# Power_Distribution_Block_Diagram.net
KiCad netlist of a schematic drawn in Altium Designer
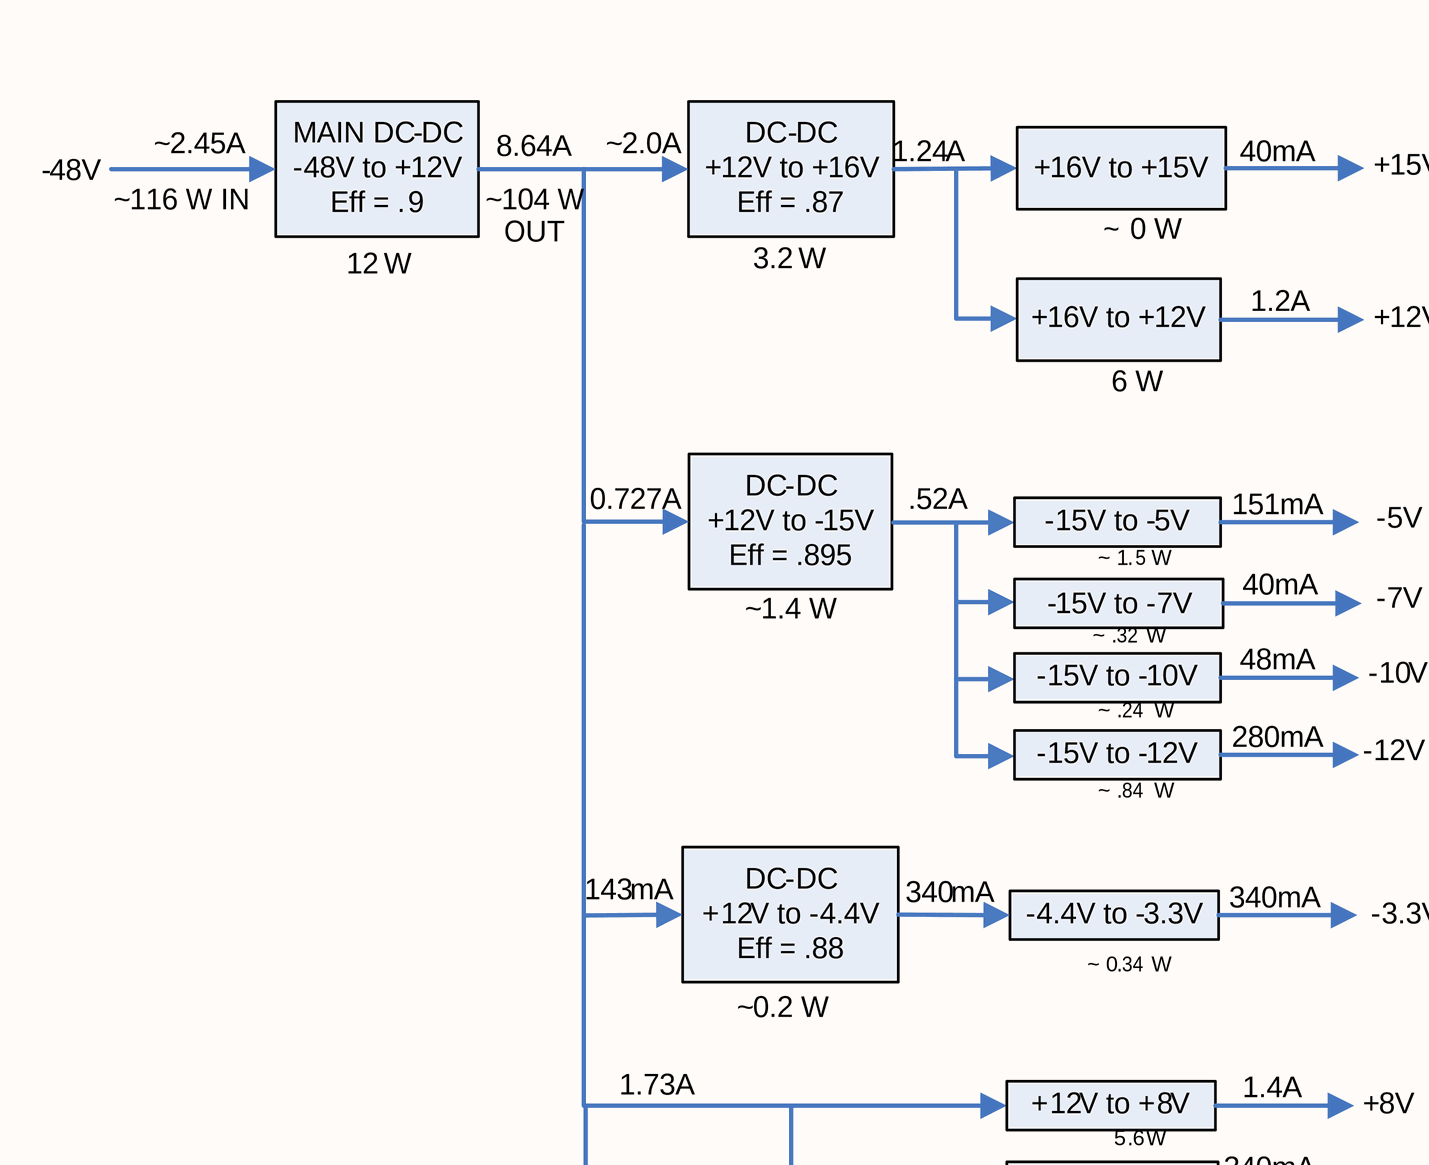
[diagram p0: Power Distribution Block Diagram.SchDoc, top left]
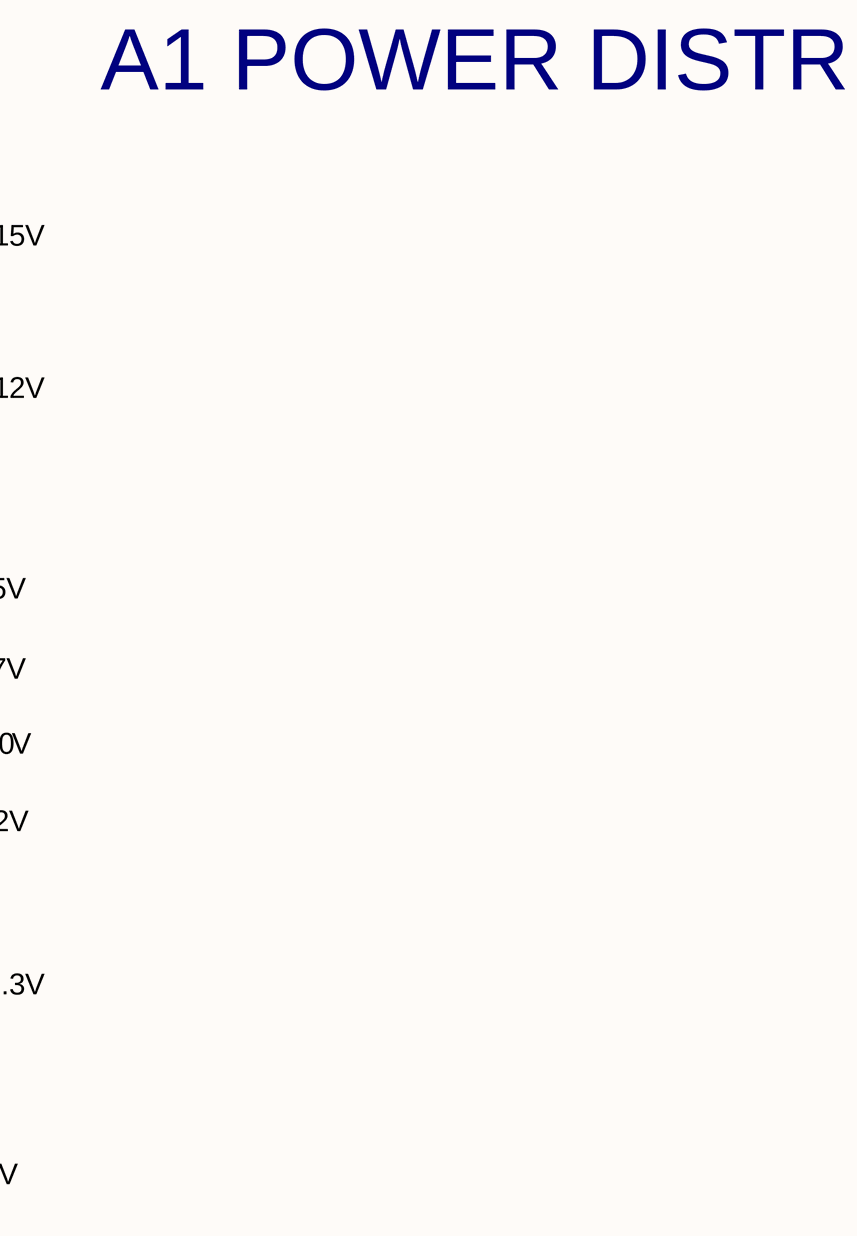
[diagram p1: Power Distribution Block Diagram.SchDoc, top middle]
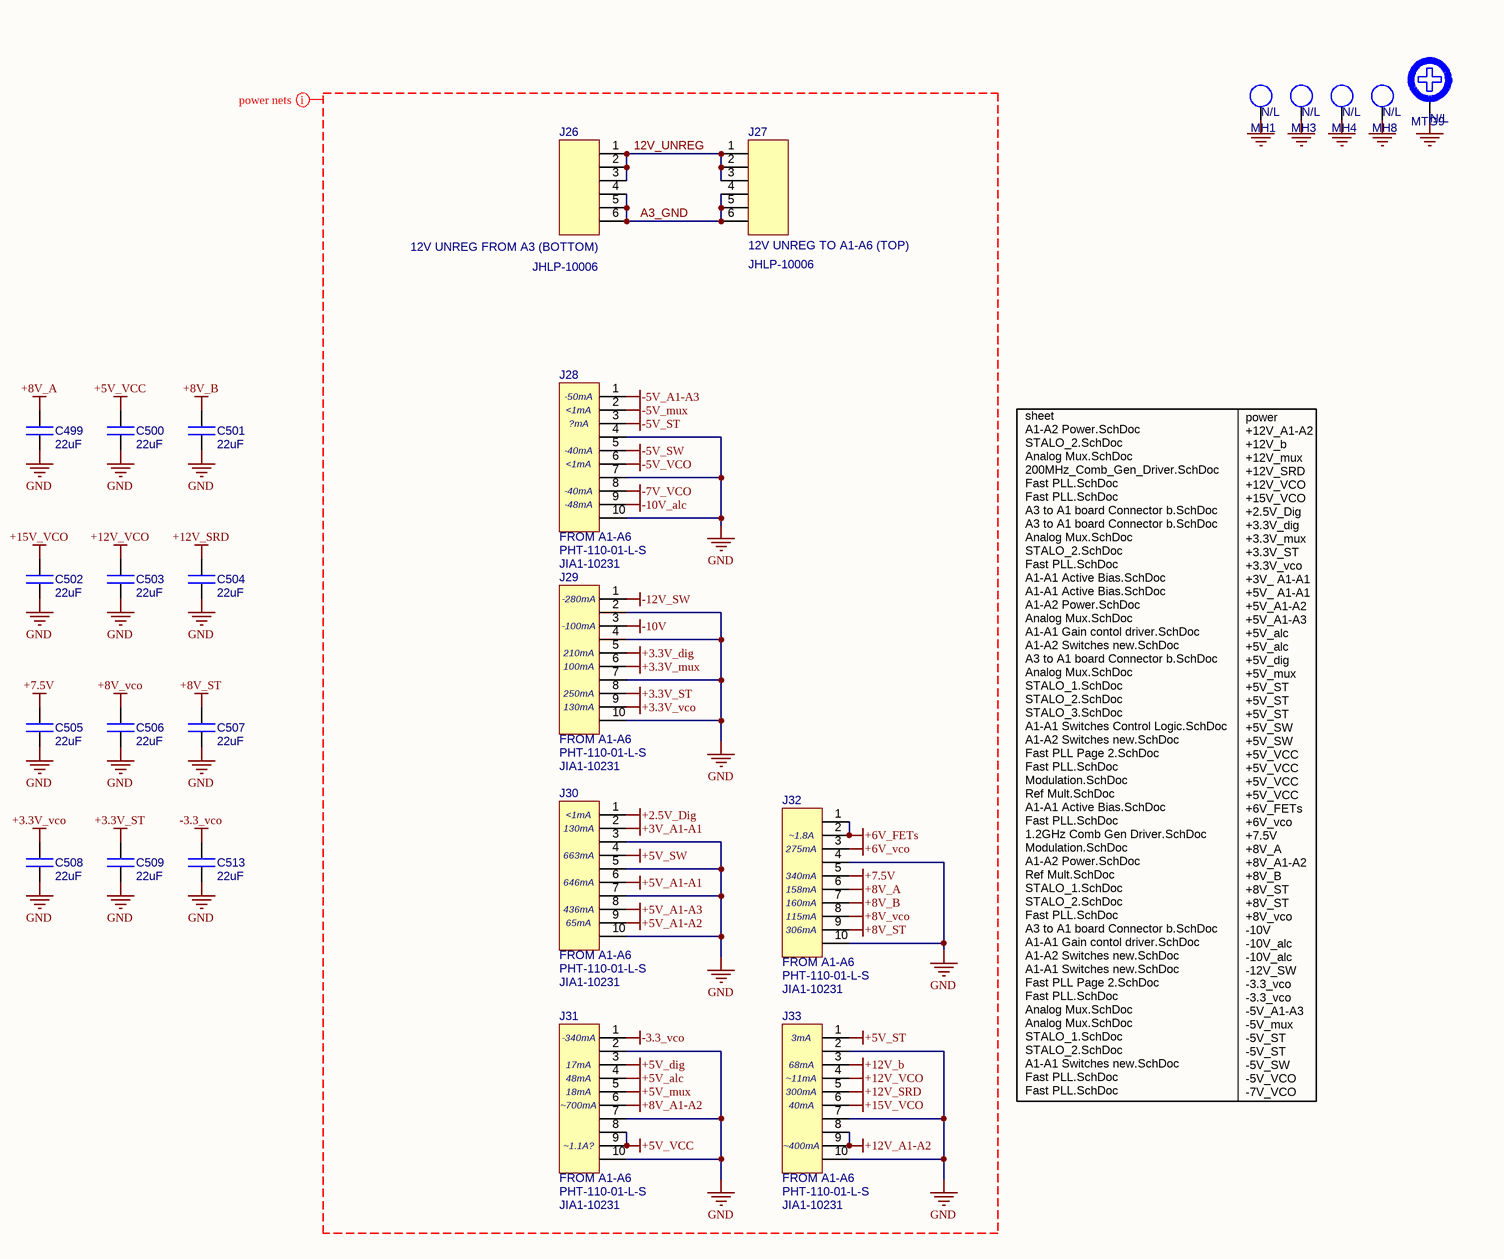
[diagram p2: Power Distribution Block Diagram.SchDoc, top right]
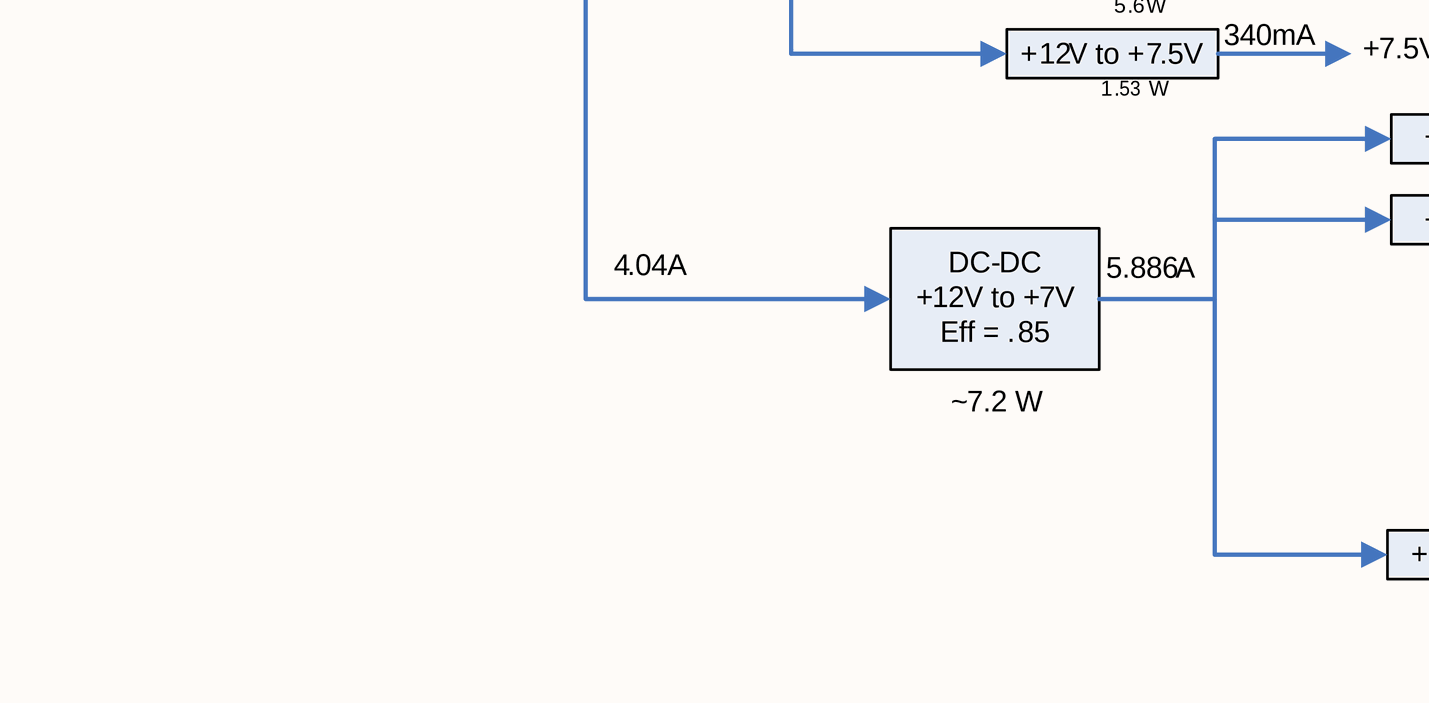
[diagram p3: Power Distribution Block Diagram.SchDoc, bottom left]
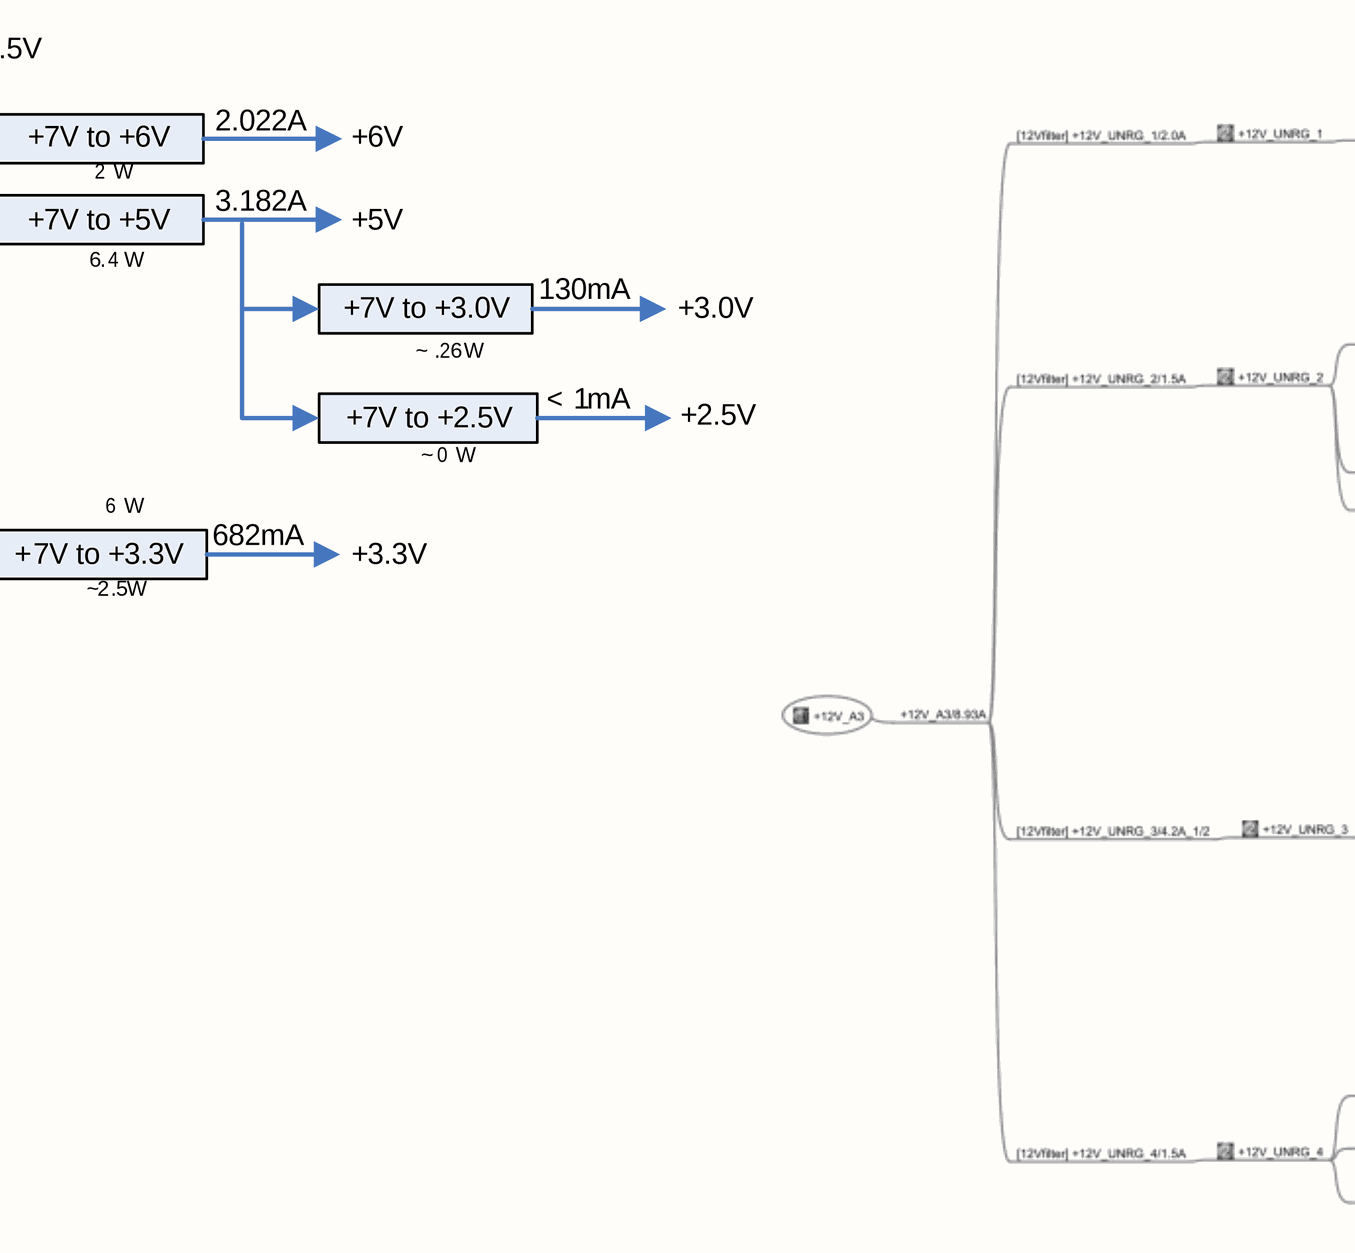
[diagram p4: Power Distribution Block Diagram.SchDoc, bottom middle]
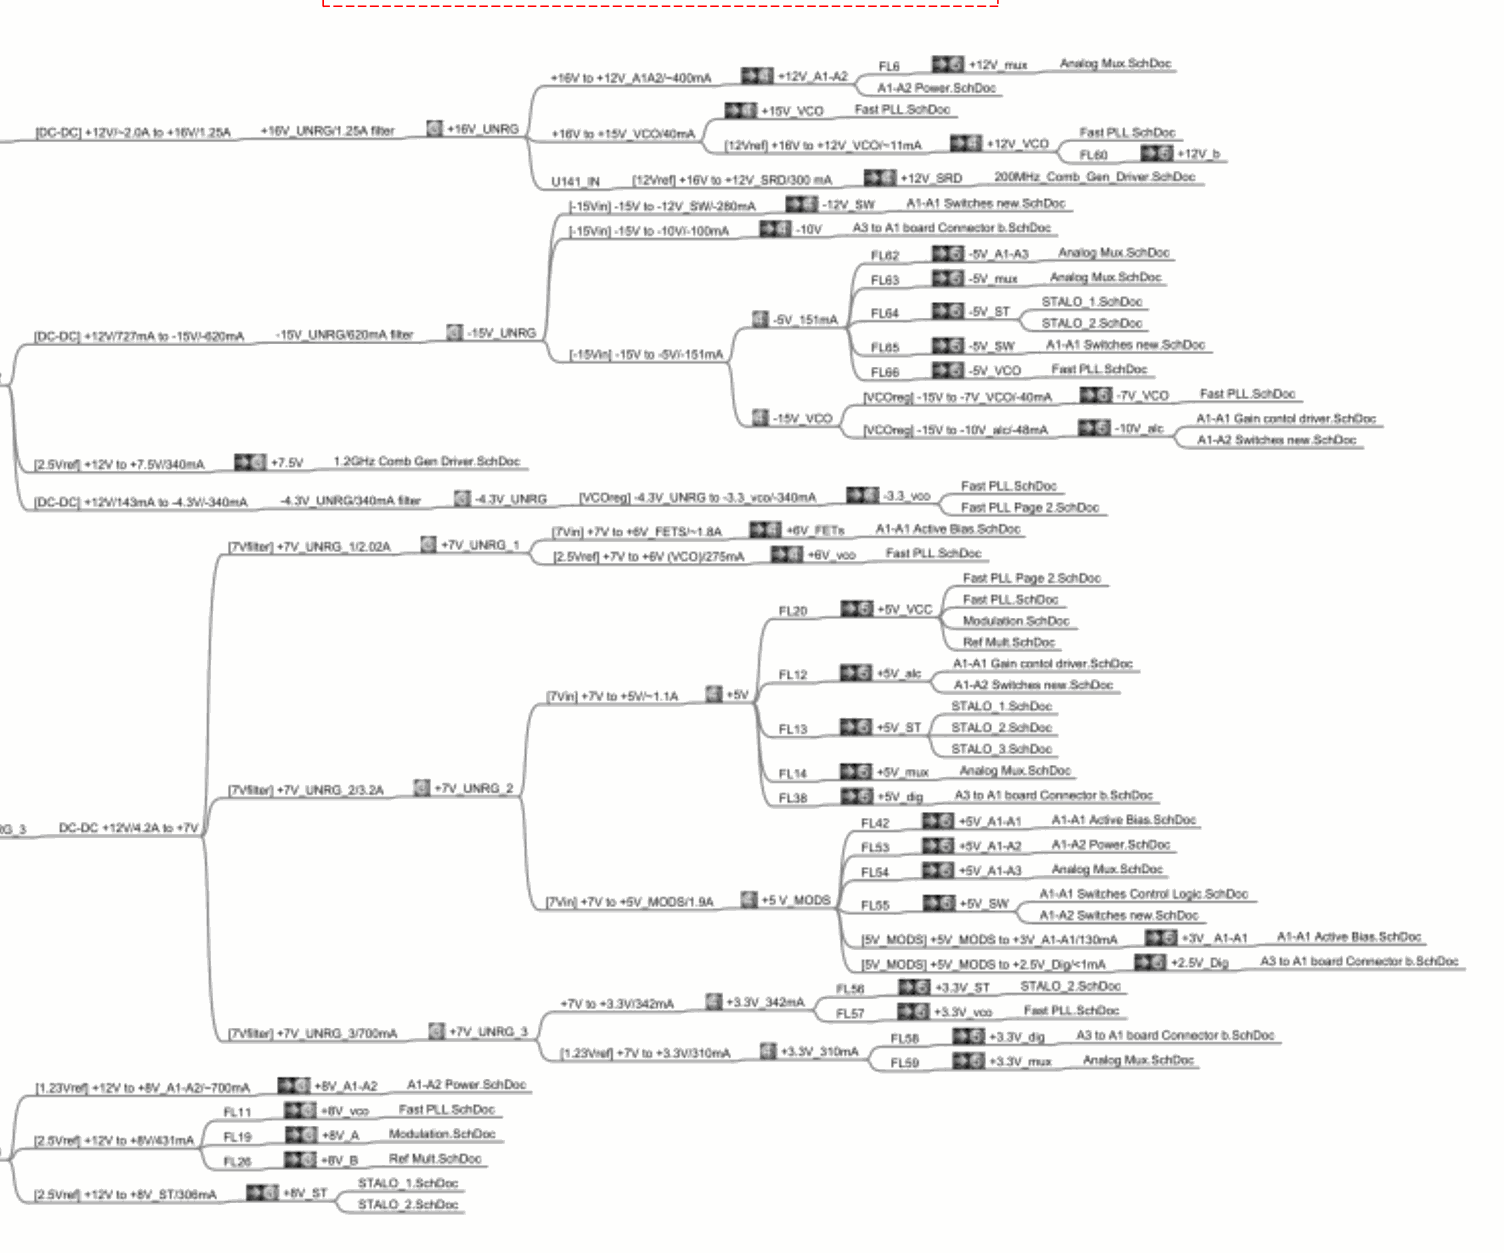
[diagram p5: Power Distribution Block Diagram.SchDoc, bottom right]

(export (version "E")
  (design (tool "Eeschema 10.0.6"))
  (components
    (comp (ref "C499")
      (value "22uF")
      (footprint "CAP-1210-N")
      (description "22uF;X5R;CERAMIC CHIP;25V;1210")
      (fields (field (name "APPROVED") "CL"))
      (libsource (lib "Giga-tronics") (part "CK60-26220"))
    )
    (comp (ref "C500")
      (value "22uF")
      (footprint "CAP-1210-N")
      (description "22uF;X5R;CERAMIC CHIP;25V;1210")
      (fields (field (name "APPROVED") "CL"))
      (libsource (lib "Giga-tronics") (part "CK60-26220"))
    )
    (comp (ref "C501")
      (value "22uF")
      (footprint "CAP-1210-N")
      (description "22uF;X5R;CERAMIC CHIP;25V;1210")
      (fields (field (name "APPROVED") "CL"))
      (libsource (lib "Giga-tronics") (part "CK60-26220"))
    )
    (comp (ref "C502")
      (value "22uF")
      (footprint "CAP-1210-N")
      (description "22uF;X5R;CERAMIC CHIP;25V;1210")
      (fields (field (name "APPROVED") "CL"))
      (libsource (lib "Giga-tronics") (part "CK60-26220"))
    )
    (comp (ref "C503")
      (value "22uF")
      (footprint "CAP-1210-N")
      (description "22uF;X5R;CERAMIC CHIP;25V;1210")
      (fields (field (name "APPROVED") "CL"))
      (libsource (lib "Giga-tronics") (part "CK60-26220"))
    )
    (comp (ref "C504")
      (value "22uF")
      (footprint "CAP-1210-N")
      (description "22uF;X5R;CERAMIC CHIP;25V;1210")
      (fields (field (name "APPROVED") "CL"))
      (libsource (lib "Giga-tronics") (part "CK60-26220"))
    )
    (comp (ref "C505")
      (value "22uF")
      (footprint "CAP-1210-N")
      (description "22uF;X5R;CERAMIC CHIP;25V;1210")
      (fields (field (name "APPROVED") "CL"))
      (libsource (lib "Giga-tronics") (part "CK60-26220"))
    )
    (comp (ref "C506")
      (value "22uF")
      (footprint "CAP-1210-N")
      (description "22uF;X5R;CERAMIC CHIP;25V;1210")
      (fields (field (name "APPROVED") "CL"))
      (libsource (lib "Giga-tronics") (part "CK60-26220"))
    )
    (comp (ref "C507")
      (value "22uF")
      (footprint "CAP-1210-N")
      (description "22uF;X5R;CERAMIC CHIP;25V;1210")
      (fields (field (name "APPROVED") "CL"))
      (libsource (lib "Giga-tronics") (part "CK60-26220"))
    )
    (comp (ref "C508")
      (value "22uF")
      (footprint "CAP-1210-N")
      (description "22uF;X5R;CERAMIC CHIP;25V;1210")
      (fields (field (name "APPROVED") "CL"))
      (libsource (lib "Giga-tronics") (part "CK60-26220"))
    )
    (comp (ref "C509")
      (value "22uF")
      (footprint "CAP-1210-N")
      (description "22uF;X5R;CERAMIC CHIP;25V;1210")
      (fields (field (name "APPROVED") "CL"))
      (libsource (lib "Giga-tronics") (part "CK60-26220"))
    )
    (comp (ref "C513")
      (value "22uF")
      (footprint "CAP-1210-N")
      (description "22uF;X5R;CERAMIC CHIP;25V;1210")
      (fields (field (name "APPROVED") "CL"))
      (libsource (lib "Giga-tronics") (part "CK60-26220"))
    )
    (comp (ref "J26")
      (value "12V UNREG FROM A3 (BOTTOM)")
      (footprint "JHLP-10006")
      (description "LOCKING HEADER;.1CNTR;6PIN STR")
      (fields (field (name "G_PN") "JHLP-10006") (field (name "APPROVED") "FV"))
      (libsource (lib "") (part "JHLP-10006_1"))
    )
    (comp (ref "J27")
      (value "12V UNREG TO A1-A6 (TOP)")
      (footprint "JHLP-10006")
      (description "LOCKING HEADER;.1CNTR;6PIN STR")
      (fields (field (name "G_PN") "JHLP-10006") (field (name "APPROVED") "FV"))
      (libsource (lib "Giga-tronics") (part "JHLP-10006"))
    )
    (comp (ref "J28")
      (value "FROM A1-A6")
      (footprint "JIA1-10231")
      (description "STRIPLINE PLUG;.1 CTR;10 PIN;SINGLE ROW;.230;PRESS FIT;GOLD")
      (fields (field (name "M_PN") "PHT-110-01-L-S") (field (name "G_PN") "JIA1-10231"))
      (libsource (lib "Giga-tronics") (part "JIA1-10231"))
    )
    (comp (ref "J29")
      (value "FROM A1-A6")
      (footprint "JIA1-10231")
      (description "STRIPLINE PLUG;.1 CTR;10 PIN;SINGLE ROW;.230;PRESS FIT;GOLD")
      (fields (field (name "M_PN") "PHT-110-01-L-S") (field (name "G_PN") "JIA1-10231"))
      (libsource (lib "Giga-tronics") (part "JIA1-10231"))
    )
    (comp (ref "J30")
      (value "FROM A1-A6")
      (footprint "JIA1-10231")
      (description "STRIPLINE PLUG;.1 CTR;10 PIN;SINGLE ROW;.230;PRESS FIT;GOLD")
      (fields (field (name "M_PN") "PHT-110-01-L-S") (field (name "G_PN") "JIA1-10231"))
      (libsource (lib "Giga-tronics") (part "JIA1-10231"))
    )
    (comp (ref "J31")
      (value "FROM A1-A6")
      (footprint "JIA1-10231")
      (description "STRIPLINE PLUG;.1 CTR;10 PIN;SINGLE ROW;.230;PRESS FIT;GOLD")
      (fields (field (name "M_PN") "PHT-110-01-L-S") (field (name "G_PN") "JIA1-10231"))
      (libsource (lib "Giga-tronics") (part "JIA1-10231"))
    )
    (comp (ref "J32")
      (value "FROM A1-A6")
      (footprint "JIA1-10231")
      (description "STRIPLINE PLUG;.1 CTR;10 PIN;SINGLE ROW;.230;PRESS FIT;GOLD")
      (fields (field (name "M_PN") "PHT-110-01-L-S") (field (name "G_PN") "JIA1-10231"))
      (libsource (lib "Giga-tronics") (part "JIA1-10231"))
    )
    (comp (ref "J33")
      (value "FROM A1-A6")
      (footprint "JIA1-10231")
      (description "STRIPLINE PLUG;.1 CTR;10 PIN;SINGLE ROW;.230;PRESS FIT;GOLD")
      (fields (field (name "M_PN") "PHT-110-01-L-S") (field (name "G_PN") "JIA1-10231"))
      (libsource (lib "Giga-tronics") (part "JIA1-10231"))
    )
    (comp (ref "MH1")
      (value "N/L")
      (footprint "MHP-250X116")
      (description "MHP-250X116")
      (fields (field (name "NOLOAD") "N/L"))
      (libsource (lib "Giga-tronics") (part "MHP-250X116"))
    )
    (comp (ref "MH3")
      (value "N/L")
      (footprint "MHP-250X116")
      (description "MHP-250X116")
      (fields (field (name "NOLOAD") "N/L"))
      (libsource (lib "Giga-tronics") (part "MHP-250X116"))
    )
    (comp (ref "MH4")
      (value "N/L")
      (footprint "MHP-250X116")
      (description "MHP-250X116")
      (fields (field (name "NOLOAD") "N/L"))
      (libsource (lib "Giga-tronics") (part "MHP-250X116"))
    )
    (comp (ref "MH8")
      (value "N/L")
      (footprint "MHP-250X116")
      (description "MHP-250X116")
      (fields (field (name "NOLOAD") "N/L"))
      (libsource (lib "Giga-tronics") (part "MHP-250X116"))
    )
    (comp (ref "MTG9")
      (value "~")
      (footprint "MHP-250X116")
      (description "MHP250X116")
      (fields (field (name "NOLOAD") "N/L"))
      (libsource (lib "Giga-tronics") (part "MHP250X116"))
    )
  )
  (nets
    (net (code "1") (name "+2.5V_Dig") (class "Default") (node (ref "J30") (pin "1") (pintype "passive")))
    (net (code "2") (name "+3.3V_ST") (class "Default")
      (node (ref "C509") (pin "2") (pintype "passive"))
      (node (ref "J29") (pin "8") (pintype "passive"))
    )
    (net (code "3") (name "+3.3V_dig") (class "Default") (node (ref "J29") (pin "5") (pintype "passive")))
    (net (code "4") (name "+3.3V_mux") (class "Default") (node (ref "J29") (pin "6") (pintype "passive")))
    (net (code "5") (name "+3.3V_vco") (class "Default")
      (node (ref "C508") (pin "2") (pintype "passive"))
      (node (ref "J29") (pin "9") (pintype "passive"))
    )
    (net (code "6") (name "+3V_A1-A1") (class "Default") (node (ref "J30") (pin "2") (pintype "passive")))
    (net (code "7") (name "+5V_A1-A1") (class "Default") (node (ref "J30") (pin "6") (pintype "passive")))
    (net (code "8") (name "+5V_A1-A2") (class "Default") (node (ref "J30") (pin "9") (pintype "passive")))
    (net (code "9") (name "+5V_A1-A3") (class "Default") (node (ref "J30") (pin "8") (pintype "passive")))
    (net (code "10") (name "+5V_ST") (class "Default") (node (ref "J33") (pin "1") (pintype "passive")))
    (net (code "11") (name "+5V_SW") (class "Default") (node (ref "J30") (pin "4") (pintype "passive")))
    (net (code "12") (name "+5V_VCC") (class "Default")
      (node (ref "C500") (pin "2") (pintype "passive"))
      (node (ref "J31") (pin "8") (pintype "passive"))
      (node (ref "J31") (pin "9") (pintype "passive"))
    )
    (net (code "13") (name "+5V_alc") (class "Default") (node (ref "J31") (pin "4") (pintype "passive")))
    (net (code "14") (name "+5V_dig") (class "Default") (node (ref "J31") (pin "3") (pintype "passive")))
    (net (code "15") (name "+5V_mux") (class "Default") (node (ref "J31") (pin "5") (pintype "passive")))
    (net (code "16") (name "+6V_FETs") (class "Default")
      (node (ref "J32") (pin "1") (pintype "passive"))
      (node (ref "J32") (pin "2") (pintype "passive"))
    )
    (net (code "17") (name "+6V_vco") (class "Default") (node (ref "J32") (pin "3") (pintype "passive")))
    (net (code "18") (name "+7.5V") (class "Default")
      (node (ref "C505") (pin "2") (pintype "passive"))
      (node (ref "J32") (pin "5") (pintype "passive"))
    )
    (net (code "19") (name "+8V_A") (class "Default")
      (node (ref "C499") (pin "2") (pintype "passive"))
      (node (ref "J32") (pin "6") (pintype "passive"))
    )
    (net (code "20") (name "+8V_A1-A2") (class "Default") (node (ref "J31") (pin "6") (pintype "passive")))
    (net (code "21") (name "+8V_B") (class "Default")
      (node (ref "C501") (pin "2") (pintype "passive"))
      (node (ref "J32") (pin "7") (pintype "passive"))
    )
    (net (code "22") (name "+8V_ST") (class "Default")
      (node (ref "C507") (pin "2") (pintype "passive"))
      (node (ref "J32") (pin "9") (pintype "passive"))
    )
    (net (code "23") (name "+8V_vco") (class "Default")
      (node (ref "C506") (pin "2") (pintype "passive"))
      (node (ref "J32") (pin "8") (pintype "passive"))
    )
    (net (code "24") (name "+12V_A1-A2") (class "Default")
      (node (ref "J33") (pin "8") (pintype "passive"))
      (node (ref "J33") (pin "9") (pintype "passive"))
    )
    (net (code "25") (name "+12V_SRD") (class "Default")
      (node (ref "C504") (pin "2") (pintype "passive"))
      (node (ref "J33") (pin "5") (pintype "passive"))
    )
    (net (code "26") (name "+12V_VCO") (class "Default")
      (node (ref "C503") (pin "2") (pintype "passive"))
      (node (ref "J33") (pin "4") (pintype "passive"))
    )
    (net (code "27") (name "+12V_b") (class "Default") (node (ref "J33") (pin "3") (pintype "passive")))
    (net (code "28") (name "+15V_VCO") (class "Default")
      (node (ref "C502") (pin "2") (pintype "passive"))
      (node (ref "J33") (pin "6") (pintype "passive"))
    )
    (net (code "29") (name "-3.3_vco") (class "Default")
      (node (ref "C513") (pin "2") (pintype "passive"))
      (node (ref "J31") (pin "1") (pintype "passive"))
    )
    (net (code "30") (name "-5V_A1-A3") (class "Default") (node (ref "J28") (pin "1") (pintype "passive")))
    (net (code "31") (name "-5V_ST") (class "Default") (node (ref "J28") (pin "3") (pintype "passive")))
    (net (code "32") (name "-5V_SW") (class "Default") (node (ref "J28") (pin "5") (pintype "passive")))
    (net (code "33") (name "-5V_VCO") (class "Default") (node (ref "J28") (pin "6") (pintype "passive")))
    (net (code "34") (name "-5V_mux") (class "Default") (node (ref "J28") (pin "2") (pintype "passive")))
    (net (code "35") (name "-7V_VCO") (class "Default") (node (ref "J28") (pin "8") (pintype "passive")))
    (net (code "36") (name "-10V") (class "Default") (node (ref "J29") (pin "3") (pintype "passive")))
    (net (code "37") (name "-10V_alc") (class "Default") (node (ref "J28") (pin "9") (pintype "passive")))
    (net (code "38") (name "-12V_SW") (class "Default") (node (ref "J29") (pin "1") (pintype "passive")))
    (net (code "39") (name "/12V_UNREG") (class "Default")
      (node (ref "J26") (pin "1") (pintype "passive"))
      (node (ref "J26") (pin "2") (pintype "passive"))
      (node (ref "J26") (pin "3") (pintype "passive"))
      (node (ref "J27") (pin "1") (pintype "passive"))
      (node (ref "J27") (pin "2") (pintype "passive"))
      (node (ref "J27") (pin "3") (pintype "passive"))
    )
    (net (code "40") (name "/A3_GND") (class "Default")
      (node (ref "J26") (pin "4") (pintype "passive"))
      (node (ref "J26") (pin "5") (pintype "passive"))
      (node (ref "J26") (pin "6") (pintype "passive"))
      (node (ref "J27") (pin "4") (pintype "passive"))
      (node (ref "J27") (pin "5") (pintype "passive"))
      (node (ref "J27") (pin "6") (pintype "passive"))
    )
    (net (code "41") (name "GND") (class "Default")
      (node (ref "C499") (pin "1") (pintype "passive"))
      (node (ref "C500") (pin "1") (pintype "passive"))
      (node (ref "C501") (pin "1") (pintype "passive"))
      (node (ref "C502") (pin "1") (pintype "passive"))
      (node (ref "C503") (pin "1") (pintype "passive"))
      (node (ref "C504") (pin "1") (pintype "passive"))
      (node (ref "C505") (pin "1") (pintype "passive"))
      (node (ref "C506") (pin "1") (pintype "passive"))
      (node (ref "C507") (pin "1") (pintype "passive"))
      (node (ref "C508") (pin "1") (pintype "passive"))
      (node (ref "C509") (pin "1") (pintype "passive"))
      (node (ref "C513") (pin "1") (pintype "passive"))
      (node (ref "J28") (pin "10") (pintype "passive"))
      (node (ref "J28") (pin "4") (pintype "passive"))
      (node (ref "J28") (pin "7") (pintype "passive"))
      (node (ref "J29") (pin "10") (pintype "passive"))
      (node (ref "J29") (pin "2") (pintype "passive"))
      (node (ref "J29") (pin "4") (pintype "passive"))
      (node (ref "J29") (pin "7") (pintype "passive"))
      (node (ref "J30") (pin "10") (pintype "passive"))
      (node (ref "J30") (pin "3") (pintype "passive"))
      (node (ref "J30") (pin "5") (pintype "passive"))
      (node (ref "J30") (pin "7") (pintype "passive"))
      (node (ref "J31") (pin "10") (pintype "passive"))
      (node (ref "J31") (pin "2") (pintype "passive"))
      (node (ref "J31") (pin "7") (pintype "passive"))
      (node (ref "J32") (pin "10") (pintype "passive"))
      (node (ref "J32") (pin "4") (pintype "passive"))
      (node (ref "J33") (pin "10") (pintype "passive"))
      (node (ref "J33") (pin "2") (pintype "passive"))
      (node (ref "J33") (pin "7") (pintype "passive"))
      (node (ref "MH1") (pin "MH") (pinfunction "1_MH") (pintype "passive"))
      (node (ref "MH3") (pin "MH") (pinfunction "1_MH") (pintype "passive"))
      (node (ref "MH4") (pin "MH") (pinfunction "1_MH") (pintype "passive"))
      (node (ref "MH8") (pin "MH") (pinfunction "1_MH") (pintype "passive"))
      (node (ref "MTG9") (pin "MH") (pinfunction "MH_MH") (pintype "passive"))
    )
  )
)
